# voltage_mode_preamplifier.net
KiCad netlist of a schematic drawn in Altium Designer
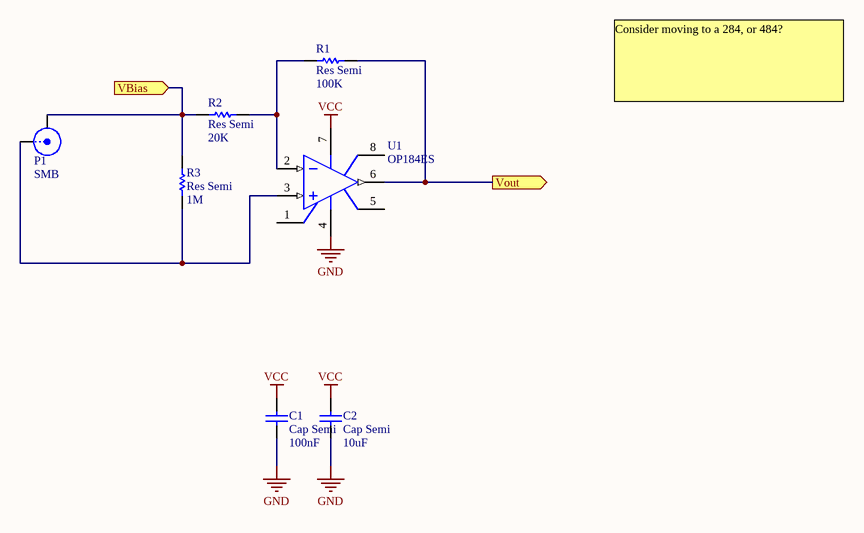
[diagram p0: voltage_mode_preamplifier.SchDoc]

(export (version "E")
  (design (tool "Eeschema 10.0.6"))
  (components
    (comp (ref "C1")
      (value "Cap Semi")
      (footprint "C0805")
      (description "Capacitor (Semiconductor SIM Model)")
      (fields (field (name "ALTIUM_VALUE") "100nF") (field (name "PUBLISHER") "Altium Limited"))
      (libsource (lib "Miscellaneous Devices") (part "Cap Semi"))
    )
    (comp (ref "C2")
      (value "Cap Semi")
      (footprint "Miscellaneous Devices:C1206")
      (description "Capacitor (Semiconductor SIM Model)")
      (fields (field (name "ALTIUM_VALUE") "10uF") (field (name "PUBLISHER") "Altium Limited"))
      (libsource (lib "Miscellaneous Devices") (part "Cap Semi"))
    )
    (comp (ref "P1")
      (value "SMB")
      (footprint "SMA_SMT")
      (description "SMB Straight Connector")
      (fields (field (name "PUBLISHER") "Altium Limited"))
      (libsource (lib "Miscellaneous Connectors") (part "SMB"))
    )
    (comp (ref "R1")
      (value "Res Semi")
      (footprint "6-0805_M")
      (description "Semiconductor Resistor")
      (fields (field (name "ALTIUM_VALUE") "100K") (field (name "PUBLISHER") "Altium Limited"))
      (libsource (lib "Miscellaneous Devices") (part "Res Semi"))
    )
    (comp (ref "R2")
      (value "Res Semi")
      (footprint "6-0805_M")
      (description "Semiconductor Resistor")
      (fields (field (name "ALTIUM_VALUE") "20K") (field (name "PUBLISHER") "Altium Limited"))
      (libsource (lib "Miscellaneous Devices") (part "Res Semi"))
    )
    (comp (ref "R3")
      (value "Res Semi")
      (footprint "6-0805_M")
      (description "Semiconductor Resistor")
      (fields (field (name "ALTIUM_VALUE") "1M") (field (name "PUBLISHER") "Altium Limited"))
      (libsource (lib "Miscellaneous Devices") (part "Res Semi"))
    )
    (comp (ref "U1")
      (value "OP184ES")
      (footprint "SO-8")
      (description "Precision Rail-to-Rail Input and Ouput Operational Amplifier")
      (fields (field (name "PUBLISHER") "Altium Limited"))
      (libsource (lib "AD Operational Amplifier") (part "OP184ES"))
    )
  )
  (nets
    (net (code "1") (name "/VBias") (class "Default")
      (node (ref "P1") (pin "2") (pinfunction "Y_2") (pintype "passive"))
      (node (ref "R2") (pin "1") (pinfunction "1_1") (pintype "passive"))
      (node (ref "R3") (pin "2") (pinfunction "2_2") (pintype "passive"))
    )
    (net (code "2") (name "/Vout") (class "Default")
      (node (ref "R1") (pin "2") (pinfunction "2_2") (pintype "passive"))
      (node (ref "U1") (pin "6") (pinfunction "OUT_6") (pintype "output"))
    )
    (net (code "3") (name "GND") (class "Default")
      (node (ref "C1") (pin "1") (pinfunction "1_1") (pintype "passive"))
      (node (ref "C2") (pin "1") (pinfunction "1_1") (pintype "passive"))
      (node (ref "U1") (pin "4") (pinfunction "V-_4") (pintype "power_in"))
    )
    (net (code "4") (name "Net-(P1-X)") (class "Default")
      (node (ref "P1") (pin "1") (pinfunction "X_1") (pintype "passive"))
      (node (ref "R3") (pin "1") (pinfunction "1_1") (pintype "passive"))
      (node (ref "U1") (pin "3") (pinfunction "IN+_3") (pintype "input"))
    )
    (net (code "5") (name "Net-(U1-IN-)") (class "Default")
      (node (ref "R1") (pin "1") (pinfunction "1_1") (pintype "passive"))
      (node (ref "R2") (pin "2") (pinfunction "2_2") (pintype "passive"))
      (node (ref "U1") (pin "2") (pinfunction "IN-_2") (pintype "input"))
    )
    (net (code "6") (name "VCC") (class "Default")
      (node (ref "C1") (pin "2") (pinfunction "2_2") (pintype "passive"))
      (node (ref "C2") (pin "2") (pinfunction "2_2") (pintype "passive"))
      (node (ref "U1") (pin "7") (pinfunction "V+_7") (pintype "power_in"))
    )
    (net (code "7") (name "unconnected-(U1-NC-Pad8)") (class "Default")
      (node (ref "U1") (pin "8") (pinfunction "NC_8") (pintype "passive"))
    )
    (net (code "8") (name "unconnected-(U1-NUL-Pad1)") (class "Default")
      (node (ref "U1") (pin "1") (pinfunction "NUL_1") (pintype "passive"))
    )
    (net (code "9") (name "unconnected-(U1-NUL-Pad5)") (class "Default")
      (node (ref "U1") (pin "5") (pinfunction "NUL_5") (pintype "passive"))
    )
  )
)
